# PCB-BI8-1x4SERCP.net
KiCad netlist of a schematic drawn in EAGLE
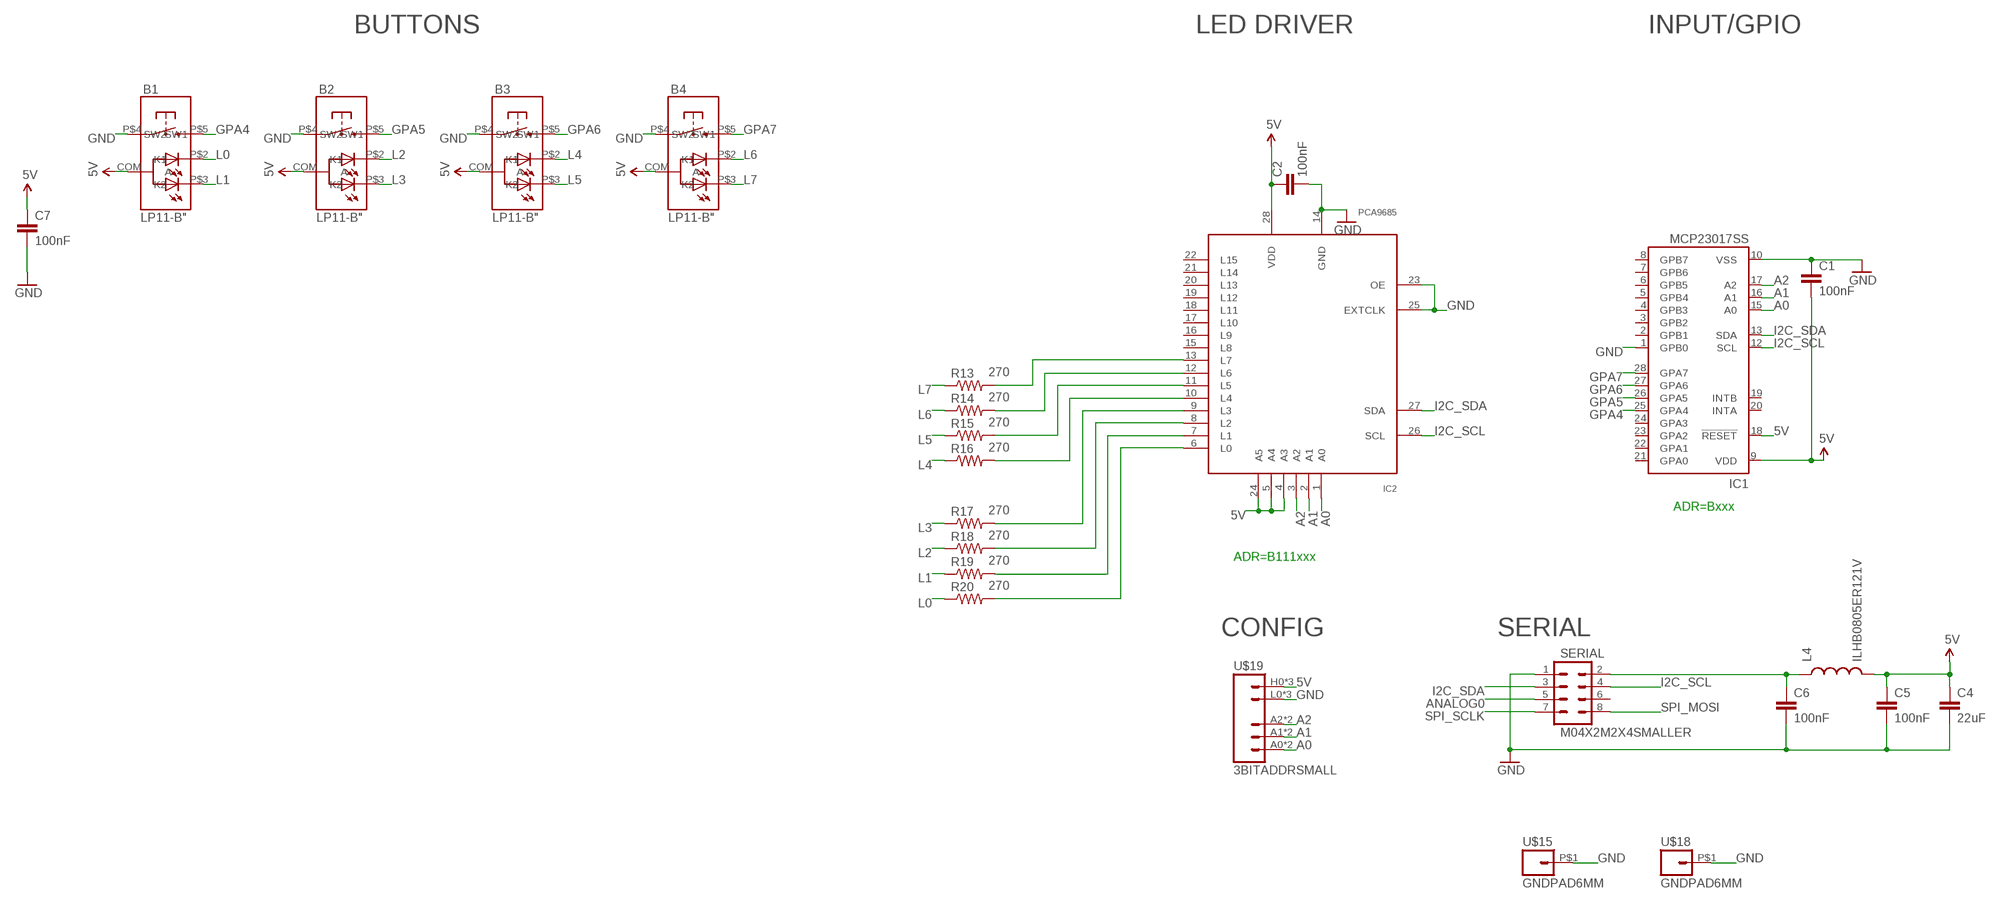
[diagram p0: schematic, sheet 1]

(export (version "E")
  (design (tool "Eeschema 10.0.6"))
  (components
    (comp (ref "B1")
      (value "LP11-B\"")
      (footprint "eagle-import:LP11")
      (libsource (lib "eagle-import") (part "LP11-B{dblquote}"))
    )
    (comp (ref "B2")
      (value "LP11-B\"")
      (footprint "eagle-import:LP11")
      (libsource (lib "eagle-import") (part "LP11-B{dblquote}"))
    )
    (comp (ref "B3")
      (value "LP11-B\"")
      (footprint "eagle-import:LP11")
      (libsource (lib "eagle-import") (part "LP11-B{dblquote}"))
    )
    (comp (ref "B4")
      (value "LP11-B\"")
      (footprint "eagle-import:LP11")
      (libsource (lib "eagle-import") (part "LP11-B{dblquote}"))
    )
    (comp (ref "C1")
      (value "100nF")
      (footprint "eagle-import:0603-CAP")
      (libsource (lib "eagle-import") (part "CAP0603-CAP"))
    )
    (comp (ref "C2")
      (value "100nF")
      (footprint "eagle-import:0603-CAP")
      (libsource (lib "eagle-import") (part "CAP0603-CAP"))
    )
    (comp (ref "C4")
      (value "22uF")
      (footprint "eagle-import:0805")
      (libsource (lib "eagle-import") (part "CAP0805"))
    )
    (comp (ref "C5")
      (value "100nF")
      (footprint "eagle-import:0603-CAP")
      (libsource (lib "eagle-import") (part "CAP0603-CAP"))
    )
    (comp (ref "C6")
      (value "100nF")
      (footprint "eagle-import:0603-CAP")
      (libsource (lib "eagle-import") (part "CAP0603-CAP"))
    )
    (comp (ref "C7")
      (value "100nF")
      (footprint "eagle-import:0603-CAP")
      (libsource (lib "eagle-import") (part "CAP0603-CAP"))
    )
    (comp (ref "IC1")
      (value "MCP23017SS")
      (footprint "eagle-import:SSOP28")
      (fields
        (field (name "MF") "MICROCHIP")
        (field (name "MPN") "MCP23017-E/SS")
        (field (name "MPN_1") "MCP23017-E/SS")
        (field (name "OC_FARNELL") "1467674")
        (field (name "OC_NEWARK") "31K2960")
      )
      (libsource (lib "eagle-import") (part "MCP23017SS"))
    )
    (comp (ref "IC2")
      (value "PCA9685")
      (footprint "eagle-import:TSSOP28")
      (libsource (lib "eagle-import") (part "PCA9685"))
    )
    (comp (ref "L4")
      (value "ILHB0805ER121V")
      (footprint "eagle-import:0805")
      (libsource (lib "eagle-import") (part "INDUCTOR0805"))
    )
    (comp (ref "R13")
      (value "270")
      (footprint "eagle-import:0603-RES")
      (libsource (lib "eagle-import") (part "RESISTOR0603-RES"))
    )
    (comp (ref "R14")
      (value "270")
      (footprint "eagle-import:0603-RES")
      (libsource (lib "eagle-import") (part "RESISTOR0603-RES"))
    )
    (comp (ref "R15")
      (value "270")
      (footprint "eagle-import:0603-RES")
      (libsource (lib "eagle-import") (part "RESISTOR0603-RES"))
    )
    (comp (ref "R16")
      (value "270")
      (footprint "eagle-import:0603-RES")
      (libsource (lib "eagle-import") (part "RESISTOR0603-RES"))
    )
    (comp (ref "R17")
      (value "270")
      (footprint "eagle-import:0603-RES")
      (libsource (lib "eagle-import") (part "RESISTOR0603-RES"))
    )
    (comp (ref "R18")
      (value "270")
      (footprint "eagle-import:0603-RES")
      (libsource (lib "eagle-import") (part "RESISTOR0603-RES"))
    )
    (comp (ref "R19")
      (value "270")
      (footprint "eagle-import:0603-RES")
      (libsource (lib "eagle-import") (part "RESISTOR0603-RES"))
    )
    (comp (ref "R20")
      (value "270")
      (footprint "eagle-import:0603-RES")
      (libsource (lib "eagle-import") (part "RESISTOR0603-RES"))
    )
    (comp (ref "SERIAL")
      (value "M04X2M2X4SMALLER")
      (footprint "eagle-import:M2X4SMALLER")
      (libsource (lib "eagle-import") (part "M04X2M2X4SMALLER"))
    )
    (comp (ref "U$15")
      (value "GNDPAD6MM")
      (footprint "eagle-import:3.2MMPAD6MM")
      (libsource (lib "eagle-import") (part "GNDPAD6MM"))
    )
    (comp (ref "U$18")
      (value "GNDPAD6MM")
      (footprint "eagle-import:3.2MMPAD6MM")
      (libsource (lib "eagle-import") (part "GNDPAD6MM"))
    )
    (comp (ref "U$19")
      (value "3BITADDRSMALL")
      (footprint "eagle-import:3BITADDR_SMALL")
      (libsource (lib "eagle-import") (part "3BITADDRSMALL"))
    )
  )
  (nets
    (net (code "1") (name "5V") (class "Default")
      (node (ref "B1") (pin "COM") (pinfunction "A_COM") (pintype "bidirectional"))
      (node (ref "B2") (pin "COM") (pinfunction "A_COM") (pintype "bidirectional"))
      (node (ref "B3") (pin "COM") (pinfunction "A_COM") (pintype "bidirectional"))
      (node (ref "B4") (pin "COM") (pinfunction "A_COM") (pintype "bidirectional"))
      (node (ref "C1") (pin "2") (pinfunction "2_2") (pintype "passive"))
      (node (ref "C2") (pin "1") (pinfunction "1_1") (pintype "passive"))
      (node (ref "C4") (pin "1") (pinfunction "1_1") (pintype "passive"))
      (node (ref "C5") (pin "1") (pinfunction "1_1") (pintype "passive"))
      (node (ref "C7") (pin "1") (pinfunction "1_1") (pintype "passive"))
      (node (ref "IC1") (pin "18") (pinfunction "~{RESET}_18") (pintype "input"))
      (node (ref "IC1") (pin "9") (pinfunction "VDD_9") (pintype "power_in"))
      (node (ref "IC2") (pin "24") (pinfunction "A5_24") (pintype "input"))
      (node (ref "IC2") (pin "28") (pinfunction "VDD_28") (pintype "power_in"))
      (node (ref "IC2") (pin "4") (pinfunction "A3_4") (pintype "input"))
      (node (ref "IC2") (pin "5") (pinfunction "A4_5") (pintype "input"))
      (node (ref "L4") (pin "2") (pinfunction "2_2") (pintype "passive"))
      (node (ref "U$19") (pin "H0") (pinfunction "VCC_H0") (pintype "passive"))
      (node (ref "U$19") (pin "H1") (pinfunction "VCC_H1") (pintype "passive"))
      (node (ref "U$19") (pin "H2") (pinfunction "VCC_H2") (pintype "passive"))
    )
    (net (code "2") (name "A0") (class "Default")
      (node (ref "IC1") (pin "15") (pinfunction "A0_15") (pintype "input"))
      (node (ref "IC2") (pin "1") (pinfunction "A0_1") (pintype "input"))
      (node (ref "U$19") (pin "A0") (pinfunction "A0_A0") (pintype "passive"))
      (node (ref "U$19") (pin "AS0") (pinfunction "A0_AS0") (pintype "passive"))
    )
    (net (code "3") (name "A1") (class "Default")
      (node (ref "IC1") (pin "16") (pinfunction "A1_16") (pintype "input"))
      (node (ref "IC2") (pin "2") (pinfunction "A1_2") (pintype "input"))
      (node (ref "U$19") (pin "A1") (pinfunction "A1_A1") (pintype "passive"))
      (node (ref "U$19") (pin "AS1") (pinfunction "A1_AS1") (pintype "passive"))
    )
    (net (code "4") (name "A2") (class "Default")
      (node (ref "IC1") (pin "17") (pinfunction "A2_17") (pintype "input"))
      (node (ref "IC2") (pin "3") (pinfunction "A2_3") (pintype "input"))
      (node (ref "U$19") (pin "A2") (pinfunction "A2_A2") (pintype "passive"))
      (node (ref "U$19") (pin "AS2") (pinfunction "A2_AS2") (pintype "passive"))
    )
    (net (code "5") (name "ANALOG0") (class "Default")
      (node (ref "SERIAL") (pin "5") (pinfunction "5_5") (pintype "passive"))
    )
    (net (code "6") (name "GND") (class "Default")
      (node (ref "B1") (pin "P$4") (pinfunction "SW1_P$4") (pintype "bidirectional"))
      (node (ref "B2") (pin "P$4") (pinfunction "SW1_P$4") (pintype "bidirectional"))
      (node (ref "B3") (pin "P$4") (pinfunction "SW1_P$4") (pintype "bidirectional"))
      (node (ref "B4") (pin "P$4") (pinfunction "SW1_P$4") (pintype "bidirectional"))
      (node (ref "C1") (pin "1") (pinfunction "1_1") (pintype "passive"))
      (node (ref "C2") (pin "2") (pinfunction "2_2") (pintype "passive"))
      (node (ref "C4") (pin "2") (pinfunction "2_2") (pintype "passive"))
      (node (ref "C5") (pin "2") (pinfunction "2_2") (pintype "passive"))
      (node (ref "C6") (pin "2") (pinfunction "2_2") (pintype "passive"))
      (node (ref "C7") (pin "2") (pinfunction "2_2") (pintype "passive"))
      (node (ref "IC1") (pin "1") (pinfunction "GPB0_1") (pintype "bidirectional"))
      (node (ref "IC1") (pin "10") (pinfunction "VSS_10") (pintype "power_in"))
      (node (ref "IC2") (pin "14") (pinfunction "GND_14") (pintype "power_in"))
      (node (ref "IC2") (pin "23") (pinfunction "OE_23") (pintype "input"))
      (node (ref "IC2") (pin "25") (pinfunction "EXTCLK_25") (pintype "input"))
      (node (ref "SERIAL") (pin "1") (pinfunction "1_1") (pintype "passive"))
      (node (ref "U$15") (pin "P$1") (pinfunction "1_P$1") (pintype "passive"))
      (node (ref "U$18") (pin "P$1") (pinfunction "1_P$1") (pintype "passive"))
      (node (ref "U$19") (pin "L0") (pinfunction "GND_L0") (pintype "passive"))
      (node (ref "U$19") (pin "L1") (pinfunction "GND_L1") (pintype "passive"))
      (node (ref "U$19") (pin "L2") (pinfunction "GND_L2") (pintype "passive"))
    )
    (net (code "7") (name "GPA4") (class "Default")
      (node (ref "B1") (pin "P$5") (pinfunction "SW2_P$5") (pintype "bidirectional"))
      (node (ref "IC1") (pin "25") (pinfunction "GPA4_25") (pintype "bidirectional"))
    )
    (net (code "8") (name "GPA5") (class "Default")
      (node (ref "B2") (pin "P$5") (pinfunction "SW2_P$5") (pintype "bidirectional"))
      (node (ref "IC1") (pin "26") (pinfunction "GPA5_26") (pintype "bidirectional"))
    )
    (net (code "9") (name "GPA6") (class "Default")
      (node (ref "B3") (pin "P$5") (pinfunction "SW2_P$5") (pintype "bidirectional"))
      (node (ref "IC1") (pin "27") (pinfunction "GPA6_27") (pintype "bidirectional"))
    )
    (net (code "10") (name "GPA7") (class "Default")
      (node (ref "B4") (pin "P$5") (pinfunction "SW2_P$5") (pintype "bidirectional"))
      (node (ref "IC1") (pin "28") (pinfunction "GPA7_28") (pintype "bidirectional"))
    )
    (net (code "11") (name "I2C_SCL") (class "Default")
      (node (ref "IC1") (pin "12") (pinfunction "SCL_12") (pintype "input"))
      (node (ref "IC2") (pin "26") (pinfunction "SCL_26") (pintype "input"))
      (node (ref "SERIAL") (pin "4") (pinfunction "4_4") (pintype "passive"))
    )
    (net (code "12") (name "I2C_SDA") (class "Default")
      (node (ref "IC1") (pin "13") (pinfunction "SDA_13") (pintype "bidirectional"))
      (node (ref "IC2") (pin "27") (pinfunction "SDA_27") (pintype "input"))
      (node (ref "SERIAL") (pin "3") (pinfunction "3_3") (pintype "passive"))
    )
    (net (code "13") (name "L0") (class "Default")
      (node (ref "B1") (pin "P$2") (pinfunction "K1_P$2") (pintype "bidirectional"))
      (node (ref "R20") (pin "1") (pinfunction "1_1") (pintype "passive"))
    )
    (net (code "14") (name "L1") (class "Default")
      (node (ref "B1") (pin "P$3") (pinfunction "K2_P$3") (pintype "bidirectional"))
      (node (ref "R19") (pin "1") (pinfunction "1_1") (pintype "passive"))
    )
    (net (code "15") (name "L2") (class "Default")
      (node (ref "B2") (pin "P$2") (pinfunction "K1_P$2") (pintype "bidirectional"))
      (node (ref "R18") (pin "1") (pinfunction "1_1") (pintype "passive"))
    )
    (net (code "16") (name "L3") (class "Default")
      (node (ref "B2") (pin "P$3") (pinfunction "K2_P$3") (pintype "bidirectional"))
      (node (ref "R17") (pin "1") (pinfunction "1_1") (pintype "passive"))
    )
    (net (code "17") (name "L4") (class "Default")
      (node (ref "B3") (pin "P$2") (pinfunction "K1_P$2") (pintype "bidirectional"))
      (node (ref "R16") (pin "1") (pinfunction "1_1") (pintype "passive"))
    )
    (net (code "18") (name "L5") (class "Default")
      (node (ref "B3") (pin "P$3") (pinfunction "K2_P$3") (pintype "bidirectional"))
      (node (ref "R15") (pin "1") (pinfunction "1_1") (pintype "passive"))
    )
    (net (code "19") (name "L6") (class "Default")
      (node (ref "B4") (pin "P$2") (pinfunction "K1_P$2") (pintype "bidirectional"))
      (node (ref "R14") (pin "1") (pinfunction "1_1") (pintype "passive"))
    )
    (net (code "20") (name "L7") (class "Default")
      (node (ref "B4") (pin "P$3") (pinfunction "K2_P$3") (pintype "bidirectional"))
      (node (ref "R13") (pin "1") (pinfunction "1_1") (pintype "passive"))
    )
    (net (code "21") (name "Net-(C6-Pad1)") (class "Default")
      (node (ref "C6") (pin "1") (pinfunction "1_1") (pintype "passive"))
      (node (ref "L4") (pin "1") (pinfunction "1_1") (pintype "passive"))
      (node (ref "SERIAL") (pin "2") (pinfunction "2_2") (pintype "passive"))
    )
    (net (code "22") (name "Net-(IC2-L0)") (class "Default")
      (node (ref "IC2") (pin "6") (pinfunction "L0_6") (pintype "output"))
      (node (ref "R20") (pin "2") (pinfunction "2_2") (pintype "passive"))
    )
    (net (code "23") (name "Net-(IC2-L1)") (class "Default")
      (node (ref "IC2") (pin "7") (pinfunction "L1_7") (pintype "output"))
      (node (ref "R19") (pin "2") (pinfunction "2_2") (pintype "passive"))
    )
    (net (code "24") (name "Net-(IC2-L2)") (class "Default")
      (node (ref "IC2") (pin "8") (pinfunction "L2_8") (pintype "output"))
      (node (ref "R18") (pin "2") (pinfunction "2_2") (pintype "passive"))
    )
    (net (code "25") (name "Net-(IC2-L3)") (class "Default")
      (node (ref "IC2") (pin "9") (pinfunction "L3_9") (pintype "output"))
      (node (ref "R17") (pin "2") (pinfunction "2_2") (pintype "passive"))
    )
    (net (code "26") (name "Net-(IC2-L4)") (class "Default")
      (node (ref "IC2") (pin "10") (pinfunction "L4_10") (pintype "output"))
      (node (ref "R16") (pin "2") (pinfunction "2_2") (pintype "passive"))
    )
    (net (code "27") (name "Net-(IC2-L5)") (class "Default")
      (node (ref "IC2") (pin "11") (pinfunction "L5_11") (pintype "output"))
      (node (ref "R15") (pin "2") (pinfunction "2_2") (pintype "passive"))
    )
    (net (code "28") (name "Net-(IC2-L6)") (class "Default")
      (node (ref "IC2") (pin "12") (pinfunction "L6_12") (pintype "output"))
      (node (ref "R14") (pin "2") (pinfunction "2_2") (pintype "passive"))
    )
    (net (code "29") (name "Net-(IC2-L7)") (class "Default")
      (node (ref "IC2") (pin "13") (pinfunction "L7_13") (pintype "output"))
      (node (ref "R13") (pin "2") (pinfunction "2_2") (pintype "passive"))
    )
    (net (code "30") (name "SPI_MOSI") (class "Default")
      (node (ref "SERIAL") (pin "8") (pinfunction "8_8") (pintype "passive"))
    )
    (net (code "31") (name "SPI_SCLK") (class "Default")
      (node (ref "SERIAL") (pin "7") (pinfunction "7_7") (pintype "passive"))
    )
    (net (code "32") (name "unconnected-(IC1-GPA0-Pad21)") (class "Default")
      (node (ref "IC1") (pin "21") (pinfunction "GPA0_21") (pintype "bidirectional"))
    )
    (net (code "33") (name "unconnected-(IC1-GPA1-Pad22)") (class "Default")
      (node (ref "IC1") (pin "22") (pinfunction "GPA1_22") (pintype "bidirectional"))
    )
    (net (code "34") (name "unconnected-(IC1-GPA2-Pad23)") (class "Default")
      (node (ref "IC1") (pin "23") (pinfunction "GPA2_23") (pintype "bidirectional"))
    )
    (net (code "35") (name "unconnected-(IC1-GPA3-Pad24)") (class "Default")
      (node (ref "IC1") (pin "24") (pinfunction "GPA3_24") (pintype "bidirectional"))
    )
    (net (code "36") (name "unconnected-(IC1-GPB1-Pad2)") (class "Default")
      (node (ref "IC1") (pin "2") (pinfunction "GPB1_2") (pintype "bidirectional"))
    )
    (net (code "37") (name "unconnected-(IC1-GPB2-Pad3)") (class "Default")
      (node (ref "IC1") (pin "3") (pinfunction "GPB2_3") (pintype "bidirectional"))
    )
    (net (code "38") (name "unconnected-(IC1-GPB3-Pad4)") (class "Default")
      (node (ref "IC1") (pin "4") (pinfunction "GPB3_4") (pintype "bidirectional"))
    )
    (net (code "39") (name "unconnected-(IC1-GPB4-Pad5)") (class "Default")
      (node (ref "IC1") (pin "5") (pinfunction "GPB4_5") (pintype "bidirectional"))
    )
    (net (code "40") (name "unconnected-(IC1-GPB5-Pad6)") (class "Default")
      (node (ref "IC1") (pin "6") (pinfunction "GPB5_6") (pintype "bidirectional"))
    )
    (net (code "41") (name "unconnected-(IC1-GPB6-Pad7)") (class "Default")
      (node (ref "IC1") (pin "7") (pinfunction "GPB6_7") (pintype "bidirectional"))
    )
    (net (code "42") (name "unconnected-(IC1-GPB7-Pad8)") (class "Default")
      (node (ref "IC1") (pin "8") (pinfunction "GPB7_8") (pintype "bidirectional"))
    )
    (net (code "43") (name "unconnected-(IC1-INTA-Pad20)") (class "Default")
      (node (ref "IC1") (pin "20") (pinfunction "INTA_20") (pintype "output"))
    )
    (net (code "44") (name "unconnected-(IC1-INTB-Pad19)") (class "Default")
      (node (ref "IC1") (pin "19") (pinfunction "INTB_19") (pintype "output"))
    )
    (net (code "45") (name "unconnected-(IC2-L8-Pad15)") (class "Default")
      (node (ref "IC2") (pin "15") (pinfunction "L8_15") (pintype "output"))
    )
    (net (code "46") (name "unconnected-(IC2-L9-Pad16)") (class "Default")
      (node (ref "IC2") (pin "16") (pinfunction "L9_16") (pintype "output"))
    )
    (net (code "47") (name "unconnected-(IC2-L10-Pad17)") (class "Default")
      (node (ref "IC2") (pin "17") (pinfunction "L10_17") (pintype "output"))
    )
    (net (code "48") (name "unconnected-(IC2-L11-Pad18)") (class "Default")
      (node (ref "IC2") (pin "18") (pinfunction "L11_18") (pintype "output"))
    )
    (net (code "49") (name "unconnected-(IC2-L12-Pad19)") (class "Default")
      (node (ref "IC2") (pin "19") (pinfunction "L12_19") (pintype "output"))
    )
    (net (code "50") (name "unconnected-(IC2-L13-Pad20)") (class "Default")
      (node (ref "IC2") (pin "20") (pinfunction "L13_20") (pintype "output"))
    )
    (net (code "51") (name "unconnected-(IC2-L14-Pad21)") (class "Default")
      (node (ref "IC2") (pin "21") (pinfunction "L14_21") (pintype "output"))
    )
    (net (code "52") (name "unconnected-(IC2-L15-Pad22)") (class "Default")
      (node (ref "IC2") (pin "22") (pinfunction "L15_22") (pintype "output"))
    )
    (net (code "53") (name "unconnected-(SERIAL-Pad6)") (class "Default")
      (node (ref "SERIAL") (pin "6") (pinfunction "6_6") (pintype "passive"))
    )
  )
)
